# LegControleur.net
KiCad netlist of a schematic drawn in Altium Designer
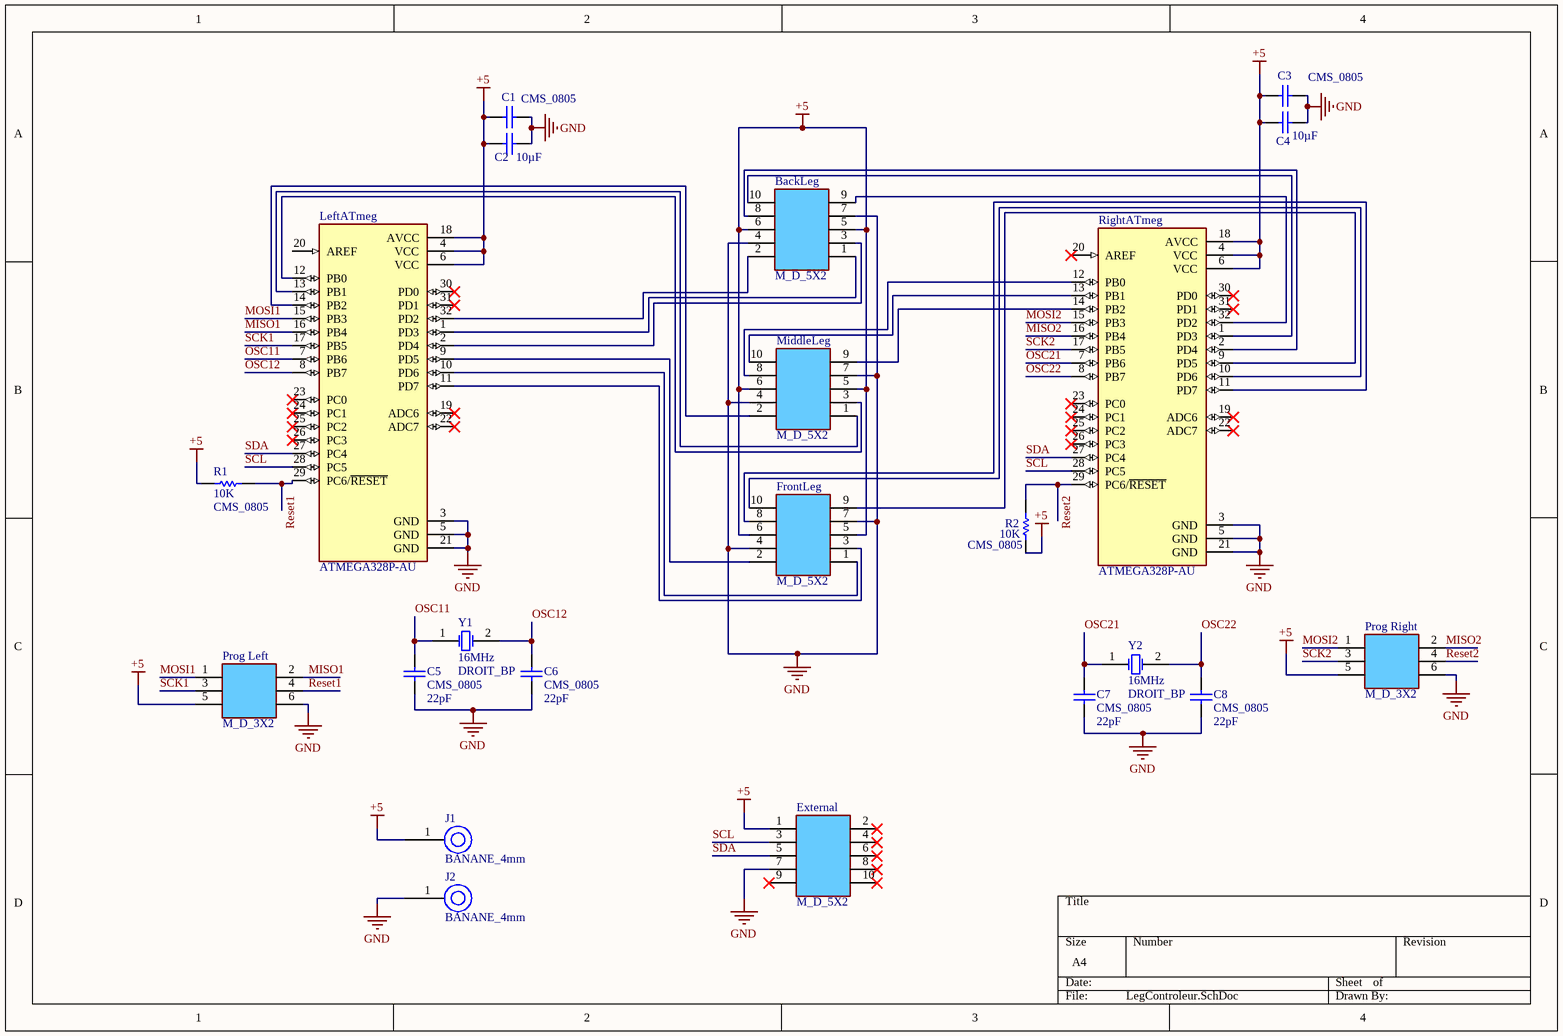
[diagram p0: LegControleur.SchDoc]

(export (version "E")
  (design (tool "Eeschema 10.0.6"))
  (components
    (comp (ref "BackLeg")
      (value "BARRETTE_5 CONTACTS_2 RANGEES_MALE_DROITE")
      (footprint "BARRETTE_5X2_M_D")
      (description "BARRETTE 5 CONTACTS 2 RANGEES MALE DROITE")
      (fields (field (name "TYPE") "M_D_5X2"))
      (libsource (lib "connecteurs") (part "BARRETTE_5 CONTACTS_2 RANGEES_MALE_DROITE"))
    )
    (comp (ref "C1")
      (value "10µF")
      (footprint "CONDENSATEUR_CMS_0805")
      (description "CONDENSATEUR CMS CERAMIQUE 0805")
      (fields (field (name "TYPE") "CMS_0805") (field (name "Comment") "CMS_0805_AVCC"))
      (libsource (lib "composants passifs") (part "CONDENSATEUR_CMS_CER_0805"))
    )
    (comp (ref "C2")
      (value "CMS_0805_VCC")
      (footprint "CONDENSATEUR_CMS_0805")
      (description "CONDENSATEUR CMS CERAMIQUE 0805")
      (libsource (lib "composants passifs") (part "CONDENSATEUR_CMS_CER_0805"))
    )
    (comp (ref "C3")
      (value "10µF")
      (footprint "CONDENSATEUR_CMS_0805")
      (description "CONDENSATEUR CMS CERAMIQUE 0805")
      (fields (field (name "TYPE") "CMS_0805") (field (name "Comment") "CMS_0805_AVCC"))
      (libsource (lib "composants passifs") (part "CONDENSATEUR_CMS_CER_0805"))
    )
    (comp (ref "C4")
      (value "CMS_0805_VCC")
      (footprint "CONDENSATEUR_CMS_0805")
      (description "CONDENSATEUR CMS CERAMIQUE 0805")
      (libsource (lib "composants passifs") (part "CONDENSATEUR_CMS_CER_0805"))
    )
    (comp (ref "C5")
      (value "22pF")
      (footprint "CONDENSATEUR_CMS_0805")
      (description "CONDENSATEUR CMS CERAMIQUE 0805")
      (fields (field (name "TYPE") "CMS_0805") (field (name "Comment") "CMS_0805"))
      (libsource (lib "composants passifs") (part "CONDENSATEUR_CMS_CER_0805"))
    )
    (comp (ref "C6")
      (value "22pF")
      (footprint "CONDENSATEUR_CMS_0805")
      (description "CONDENSATEUR CMS CERAMIQUE 0805")
      (fields (field (name "TYPE") "CMS_0805") (field (name "Comment") "CMS_0805"))
      (libsource (lib "composants passifs") (part "CONDENSATEUR_CMS_CER_0805"))
    )
    (comp (ref "C7")
      (value "22pF")
      (footprint "CONDENSATEUR_CMS_0805")
      (description "CONDENSATEUR CMS CERAMIQUE 0805")
      (fields (field (name "TYPE") "CMS_0805") (field (name "Comment") "CMS_0805"))
      (libsource (lib "composants passifs") (part "CONDENSATEUR_CMS_CER_0805"))
    )
    (comp (ref "C8")
      (value "22pF")
      (footprint "CONDENSATEUR_CMS_0805")
      (description "CONDENSATEUR CMS CERAMIQUE 0805")
      (fields (field (name "TYPE") "CMS_0805") (field (name "Comment") "CMS_0805"))
      (libsource (lib "composants passifs") (part "CONDENSATEUR_CMS_CER_0805"))
    )
    (comp (ref "External")
      (value "BARRETTE_5 CONTACTS_2 RANGEES_MALE_DROITE")
      (footprint "BARRETTE_5X2_M_D")
      (description "BARRETTE 5 CONTACTS 2 RANGEES MALE DROITE")
      (fields (field (name "TYPE") "M_D_5X2"))
      (libsource (lib "") (part "BARRETTE_5 CONTACTS_2 RANGEES_MALE_DROITE_1"))
    )
    (comp (ref "FrontLeg")
      (value "BARRETTE_5 CONTACTS_2 RANGEES_MALE_DROITE")
      (footprint "BARRETTE_5X2_M_D")
      (description "BARRETTE 5 CONTACTS 2 RANGEES MALE DROITE")
      (fields (field (name "TYPE") "M_D_5X2"))
      (libsource (lib "connecteurs") (part "BARRETTE_5 CONTACTS_2 RANGEES_MALE_DROITE"))
    )
    (comp (ref "J1")
      (value "Alim 5v")
      (footprint "DOUILLE_BANANE_4mm")
      (description "DOUILLE BANANE 4 mm")
      (fields (field (name "TYPE") "BANANE_4mm"))
      (libsource (lib "connecteurs") (part "DOUILLE_BANANE_4mm"))
    )
    (comp (ref "J2")
      (value "Alim GND")
      (footprint "DOUILLE_BANANE_4mm")
      (description "DOUILLE BANANE 4 mm")
      (fields (field (name "TYPE") "BANANE_4mm"))
      (libsource (lib "connecteurs") (part "DOUILLE_BANANE_4mm"))
    )
    (comp (ref "LeftATmeg")
      (value "ATMEGA328P-AU")
      (footprint "QFP80P900X900X120-32N")
      (description "AVR AVRÂ® ATmega Microcontroller IC 8-Bit 20MHz 32KB (16K x 16) FLASH 32-TQFP (7x7)")
      (fields (field (name "MF") "Microchip Technology"))
      (libsource (lib "ATMEGA328P-AU") (part "ATMEGA328P-AU"))
    )
    (comp (ref "MiddleLeg")
      (value "BARRETTE_5 CONTACTS_2 RANGEES_MALE_DROITE")
      (footprint "BARRETTE_5X2_M_D")
      (description "BARRETTE 5 CONTACTS 2 RANGEES MALE DROITE")
      (fields (field (name "TYPE") "M_D_5X2"))
      (libsource (lib "connecteurs") (part "BARRETTE_5 CONTACTS_2 RANGEES_MALE_DROITE"))
    )
    (comp (ref "Prog Left")
      (value "BARRETTE_3 CONTACTS_2 RANGEES_MALE_DROITE")
      (footprint "BARRETTE_3X2_M_D")
      (description "BARRETTE 3 CONTACTS 2 RANGEES MALE DROITE")
      (fields (field (name "TYPE") "M_D_3X2"))
      (libsource (lib "connecteurs") (part "BARRETTE_3 CONTACTS_2 RANGEES_MALE_DROITE"))
    )
    (comp (ref "Prog Right")
      (value "BARRETTE_3 CONTACTS_2 RANGEES_MALE_DROITE")
      (footprint "BARRETTE_3X2_M_D")
      (description "BARRETTE 3 CONTACTS 2 RANGEES MALE DROITE")
      (fields (field (name "TYPE") "M_D_3X2"))
      (libsource (lib "connecteurs") (part "BARRETTE_3 CONTACTS_2 RANGEES_MALE_DROITE"))
    )
    (comp (ref "R1")
      (value "10K")
      (footprint "RESISTANCE_CMS_0805")
      (description "RESISTANCE CMS 0805")
      (fields (field (name "TYPE") "CMS_0805") (field (name "Comment") "RESISTANCE_CMS_0805"))
      (libsource (lib "composants passifs") (part "RESISTANCE_CMS_0805"))
    )
    (comp (ref "R2")
      (value "10K")
      (footprint "RESISTANCE_CMS_0805")
      (description "RESISTANCE CMS 0805")
      (fields (field (name "TYPE") "CMS_0805") (field (name "Comment") "RESISTANCE_CMS_0805"))
      (libsource (lib "composants passifs") (part "RESISTANCE_CMS_0805"))
    )
    (comp (ref "RightATmeg")
      (value "ATMEGA328P-AU")
      (footprint "QFP80P900X900X120-32N")
      (description "AVR AVRÂ® ATmega Microcontroller IC 8-Bit 20MHz 32KB (16K x 16) FLASH 32-TQFP (7x7)")
      (fields (field (name "MF") "Microchip Technology"))
      (libsource (lib "ATMEGA328P-AU") (part "ATMEGA328P-AU"))
    )
    (comp (ref "Y1")
      (value "16MHz")
      (footprint "QUARTZ_DROIT_BP")
      (description "QUARTZ DROIT BAS PROFIL")
      (fields (field (name "TYPE") "DROIT_BP") (field (name "Comment") "QUARTZ_DROIT_BAS_PROFIL"))
      (libsource (lib "composants passifs") (part "QUARTZ_DROIT_BAS_PROFIL"))
    )
    (comp (ref "Y2")
      (value "16MHz")
      (footprint "QUARTZ_DROIT_BP")
      (description "QUARTZ DROIT BAS PROFIL")
      (fields (field (name "TYPE") "DROIT_BP") (field (name "Comment") "QUARTZ_DROIT_BAS_PROFIL"))
      (libsource (lib "composants passifs") (part "QUARTZ_DROIT_BAS_PROFIL"))
    )
  )
  (nets
    (net (code "1") (name "+5") (class "Default")
      (node (ref "BackLeg") (pin "5") (pinfunction "5_5") (pintype "passive"))
      (node (ref "BackLeg") (pin "6") (pinfunction "6_6") (pintype "passive"))
      (node (ref "C1") (pin "2") (pinfunction "2_2") (pintype "passive"))
      (node (ref "C2") (pin "2") (pinfunction "2_2") (pintype "passive"))
      (node (ref "C3") (pin "2") (pinfunction "2_2") (pintype "passive"))
      (node (ref "C4") (pin "2") (pinfunction "2_2") (pintype "passive"))
      (node (ref "External") (pin "1") (pinfunction "1_1") (pintype "passive"))
      (node (ref "FrontLeg") (pin "5") (pinfunction "5_5") (pintype "passive"))
      (node (ref "FrontLeg") (pin "6") (pinfunction "6_6") (pintype "passive"))
      (node (ref "J1") (pin "1") (pinfunction "1_1") (pintype "passive"))
      (node (ref "LeftATmeg") (pin "18") (pinfunction "AVCC_18") (pintype "power_in"))
      (node (ref "LeftATmeg") (pin "4") (pinfunction "VCC_4") (pintype "power_in"))
      (node (ref "LeftATmeg") (pin "6") (pinfunction "VCC_6") (pintype "power_in"))
      (node (ref "MiddleLeg") (pin "5") (pinfunction "5_5") (pintype "passive"))
      (node (ref "MiddleLeg") (pin "6") (pinfunction "6_6") (pintype "passive"))
      (node (ref "Prog Left") (pin "5") (pinfunction "5_5") (pintype "passive"))
      (node (ref "Prog Right") (pin "5") (pinfunction "5_5") (pintype "passive"))
      (node (ref "R1") (pin "1") (pinfunction "1_1") (pintype "passive"))
      (node (ref "R2") (pin "1") (pinfunction "1_1") (pintype "passive"))
      (node (ref "RightATmeg") (pin "18") (pinfunction "AVCC_18") (pintype "power_in"))
      (node (ref "RightATmeg") (pin "4") (pinfunction "VCC_4") (pintype "power_in"))
      (node (ref "RightATmeg") (pin "6") (pinfunction "VCC_6") (pintype "power_in"))
    )
    (net (code "2") (name "/MISO1") (class "Default")
      (node (ref "LeftATmeg") (pin "16") (pinfunction "PB4_16") (pintype "bidirectional"))
      (node (ref "Prog Left") (pin "2") (pinfunction "2_2") (pintype "passive"))
    )
    (net (code "3") (name "/MISO2") (class "Default")
      (node (ref "Prog Right") (pin "2") (pinfunction "2_2") (pintype "passive"))
      (node (ref "RightATmeg") (pin "16") (pinfunction "PB4_16") (pintype "bidirectional"))
    )
    (net (code "4") (name "/MOSI1") (class "Default")
      (node (ref "LeftATmeg") (pin "15") (pinfunction "PB3_15") (pintype "bidirectional"))
      (node (ref "Prog Left") (pin "1") (pinfunction "1_1") (pintype "passive"))
    )
    (net (code "5") (name "/MOSI2") (class "Default")
      (node (ref "Prog Right") (pin "1") (pinfunction "1_1") (pintype "passive"))
      (node (ref "RightATmeg") (pin "15") (pinfunction "PB3_15") (pintype "bidirectional"))
    )
    (net (code "6") (name "/OSC11") (class "Default")
      (node (ref "C5") (pin "2") (pinfunction "2_2") (pintype "passive"))
      (node (ref "LeftATmeg") (pin "7") (pinfunction "PB6_7") (pintype "bidirectional"))
      (node (ref "Y1") (pin "1") (pinfunction "OSC1_1") (pintype "passive"))
    )
    (net (code "7") (name "/OSC12") (class "Default")
      (node (ref "C6") (pin "2") (pinfunction "2_2") (pintype "passive"))
      (node (ref "LeftATmeg") (pin "8") (pinfunction "PB7_8") (pintype "bidirectional"))
      (node (ref "Y1") (pin "2") (pinfunction "OSC2_2") (pintype "passive"))
    )
    (net (code "8") (name "/OSC21") (class "Default")
      (node (ref "C7") (pin "2") (pinfunction "2_2") (pintype "passive"))
      (node (ref "RightATmeg") (pin "7") (pinfunction "PB6_7") (pintype "bidirectional"))
      (node (ref "Y2") (pin "1") (pinfunction "OSC1_1") (pintype "passive"))
    )
    (net (code "9") (name "/OSC22") (class "Default")
      (node (ref "C8") (pin "2") (pinfunction "2_2") (pintype "passive"))
      (node (ref "RightATmeg") (pin "8") (pinfunction "PB7_8") (pintype "bidirectional"))
      (node (ref "Y2") (pin "2") (pinfunction "OSC2_2") (pintype "passive"))
    )
    (net (code "10") (name "/Reset1") (class "Default")
      (node (ref "LeftATmeg") (pin "29") (pinfunction "PC6/~{RESET}_29") (pintype "bidirectional"))
      (node (ref "Prog Left") (pin "4") (pinfunction "4_4") (pintype "passive"))
      (node (ref "R1") (pin "2") (pinfunction "2_2") (pintype "passive"))
    )
    (net (code "11") (name "/Reset2") (class "Default")
      (node (ref "Prog Right") (pin "4") (pinfunction "4_4") (pintype "passive"))
      (node (ref "R2") (pin "2") (pinfunction "2_2") (pintype "passive"))
      (node (ref "RightATmeg") (pin "29") (pinfunction "PC6/~{RESET}_29") (pintype "bidirectional"))
    )
    (net (code "12") (name "/SCK1") (class "Default")
      (node (ref "LeftATmeg") (pin "17") (pinfunction "PB5_17") (pintype "bidirectional"))
      (node (ref "Prog Left") (pin "3") (pinfunction "3_3") (pintype "passive"))
    )
    (net (code "13") (name "/SCK2") (class "Default")
      (node (ref "Prog Right") (pin "3") (pinfunction "3_3") (pintype "passive"))
      (node (ref "RightATmeg") (pin "17") (pinfunction "PB5_17") (pintype "bidirectional"))
    )
    (net (code "14") (name "/SCL") (class "Default")
      (node (ref "External") (pin "3") (pinfunction "3_3") (pintype "passive"))
      (node (ref "LeftATmeg") (pin "28") (pinfunction "PC5_28") (pintype "bidirectional"))
      (node (ref "RightATmeg") (pin "28") (pinfunction "PC5_28") (pintype "bidirectional"))
    )
    (net (code "15") (name "/SDA") (class "Default")
      (node (ref "External") (pin "5") (pinfunction "5_5") (pintype "passive"))
      (node (ref "LeftATmeg") (pin "27") (pinfunction "PC4_27") (pintype "bidirectional"))
      (node (ref "RightATmeg") (pin "27") (pinfunction "PC4_27") (pintype "bidirectional"))
    )
    (net (code "16") (name "GND") (class "Default")
      (node (ref "BackLeg") (pin "4") (pinfunction "4_4") (pintype "passive"))
      (node (ref "BackLeg") (pin "7") (pinfunction "7_7") (pintype "passive"))
      (node (ref "C1") (pin "1") (pinfunction "1_1") (pintype "passive"))
      (node (ref "C2") (pin "1") (pinfunction "1_1") (pintype "passive"))
      (node (ref "C3") (pin "1") (pinfunction "1_1") (pintype "passive"))
      (node (ref "C4") (pin "1") (pinfunction "1_1") (pintype "passive"))
      (node (ref "C5") (pin "1") (pinfunction "1_1") (pintype "passive"))
      (node (ref "C6") (pin "1") (pinfunction "1_1") (pintype "passive"))
      (node (ref "C7") (pin "1") (pinfunction "1_1") (pintype "passive"))
      (node (ref "C8") (pin "1") (pinfunction "1_1") (pintype "passive"))
      (node (ref "External") (pin "7") (pinfunction "7_7") (pintype "passive"))
      (node (ref "FrontLeg") (pin "4") (pinfunction "4_4") (pintype "passive"))
      (node (ref "FrontLeg") (pin "7") (pinfunction "7_7") (pintype "passive"))
      (node (ref "J2") (pin "1") (pinfunction "1_1") (pintype "passive"))
      (node (ref "LeftATmeg") (pin "21") (pinfunction "GND_21") (pintype "power_in"))
      (node (ref "LeftATmeg") (pin "3") (pinfunction "GND_3") (pintype "power_in"))
      (node (ref "LeftATmeg") (pin "5") (pinfunction "GND_5") (pintype "power_in"))
      (node (ref "MiddleLeg") (pin "4") (pinfunction "4_4") (pintype "passive"))
      (node (ref "MiddleLeg") (pin "7") (pinfunction "7_7") (pintype "passive"))
      (node (ref "Prog Left") (pin "6") (pinfunction "6_6") (pintype "passive"))
      (node (ref "Prog Right") (pin "6") (pinfunction "6_6") (pintype "passive"))
      (node (ref "RightATmeg") (pin "21") (pinfunction "GND_21") (pintype "power_in"))
      (node (ref "RightATmeg") (pin "3") (pinfunction "GND_3") (pintype "power_in"))
      (node (ref "RightATmeg") (pin "5") (pinfunction "GND_5") (pintype "power_in"))
    )
    (net (code "17") (name "Net-(LeftATmeg-PB0)") (class "Default")
      (node (ref "LeftATmeg") (pin "12") (pinfunction "PB0_12") (pintype "bidirectional"))
      (node (ref "MiddleLeg") (pin "3") (pinfunction "3_3") (pintype "passive"))
    )
    (net (code "18") (name "Net-(LeftATmeg-PB1)") (class "Default")
      (node (ref "LeftATmeg") (pin "13") (pinfunction "PB1_13") (pintype "bidirectional"))
      (node (ref "MiddleLeg") (pin "1") (pinfunction "1_1") (pintype "passive"))
    )
    (net (code "19") (name "Net-(LeftATmeg-PB2)") (class "Default")
      (node (ref "LeftATmeg") (pin "14") (pinfunction "PB2_14") (pintype "bidirectional"))
      (node (ref "MiddleLeg") (pin "2") (pinfunction "2_2") (pintype "passive"))
    )
    (net (code "20") (name "Net-(LeftATmeg-PD2)") (class "Default")
      (node (ref "BackLeg") (pin "2") (pinfunction "2_2") (pintype "passive"))
      (node (ref "LeftATmeg") (pin "32") (pinfunction "PD2_32") (pintype "bidirectional"))
    )
    (net (code "21") (name "Net-(LeftATmeg-PD3)") (class "Default")
      (node (ref "BackLeg") (pin "1") (pinfunction "1_1") (pintype "passive"))
      (node (ref "LeftATmeg") (pin "1") (pinfunction "PD3_1") (pintype "bidirectional"))
    )
    (net (code "22") (name "Net-(LeftATmeg-PD4)") (class "Default")
      (node (ref "BackLeg") (pin "3") (pinfunction "3_3") (pintype "passive"))
      (node (ref "LeftATmeg") (pin "2") (pinfunction "PD4_2") (pintype "bidirectional"))
    )
    (net (code "23") (name "Net-(LeftATmeg-PD5)") (class "Default")
      (node (ref "FrontLeg") (pin "2") (pinfunction "2_2") (pintype "passive"))
      (node (ref "LeftATmeg") (pin "9") (pinfunction "PD5_9") (pintype "bidirectional"))
    )
    (net (code "24") (name "Net-(LeftATmeg-PD6)") (class "Default")
      (node (ref "FrontLeg") (pin "1") (pinfunction "1_1") (pintype "passive"))
      (node (ref "LeftATmeg") (pin "10") (pinfunction "PD6_10") (pintype "bidirectional"))
    )
    (net (code "25") (name "Net-(LeftATmeg-PD7)") (class "Default")
      (node (ref "FrontLeg") (pin "3") (pinfunction "3_3") (pintype "passive"))
      (node (ref "LeftATmeg") (pin "11") (pinfunction "PD7_11") (pintype "bidirectional"))
    )
    (net (code "26") (name "Net-(RightATmeg-PB0)") (class "Default")
      (node (ref "MiddleLeg") (pin "8") (pinfunction "8_8") (pintype "passive"))
      (node (ref "RightATmeg") (pin "12") (pinfunction "PB0_12") (pintype "bidirectional"))
    )
    (net (code "27") (name "Net-(RightATmeg-PB1)") (class "Default")
      (node (ref "MiddleLeg") (pin "10") (pinfunction "10_10") (pintype "passive"))
      (node (ref "RightATmeg") (pin "13") (pinfunction "PB1_13") (pintype "bidirectional"))
    )
    (net (code "28") (name "Net-(RightATmeg-PB2)") (class "Default")
      (node (ref "MiddleLeg") (pin "9") (pinfunction "9_9") (pintype "passive"))
      (node (ref "RightATmeg") (pin "14") (pinfunction "PB2_14") (pintype "bidirectional"))
    )
    (net (code "29") (name "Net-(RightATmeg-PD2)") (class "Default")
      (node (ref "BackLeg") (pin "9") (pinfunction "9_9") (pintype "passive"))
      (node (ref "RightATmeg") (pin "32") (pinfunction "PD2_32") (pintype "bidirectional"))
    )
    (net (code "30") (name "Net-(RightATmeg-PD3)") (class "Default")
      (node (ref "BackLeg") (pin "10") (pinfunction "10_10") (pintype "passive"))
      (node (ref "RightATmeg") (pin "1") (pinfunction "PD3_1") (pintype "bidirectional"))
    )
    (net (code "31") (name "Net-(RightATmeg-PD4)") (class "Default")
      (node (ref "BackLeg") (pin "8") (pinfunction "8_8") (pintype "passive"))
      (node (ref "RightATmeg") (pin "2") (pinfunction "PD4_2") (pintype "bidirectional"))
    )
    (net (code "32") (name "Net-(RightATmeg-PD5)") (class "Default")
      (node (ref "FrontLeg") (pin "9") (pinfunction "9_9") (pintype "passive"))
      (node (ref "RightATmeg") (pin "9") (pinfunction "PD5_9") (pintype "bidirectional"))
    )
    (net (code "33") (name "Net-(RightATmeg-PD6)") (class "Default")
      (node (ref "FrontLeg") (pin "10") (pinfunction "10_10") (pintype "passive"))
      (node (ref "RightATmeg") (pin "10") (pinfunction "PD6_10") (pintype "bidirectional"))
    )
    (net (code "34") (name "Net-(RightATmeg-PD7)") (class "Default")
      (node (ref "FrontLeg") (pin "8") (pinfunction "8_8") (pintype "passive"))
      (node (ref "RightATmeg") (pin "11") (pinfunction "PD7_11") (pintype "bidirectional"))
    )
    (net (code "35") (name "unconnected-(External-Pad2)") (class "Default")
      (node (ref "External") (pin "2") (pinfunction "2_2") (pintype "passive+no_connect"))
    )
    (net (code "36") (name "unconnected-(External-Pad4)") (class "Default")
      (node (ref "External") (pin "4") (pinfunction "4_4") (pintype "passive+no_connect"))
    )
    (net (code "37") (name "unconnected-(External-Pad6)") (class "Default")
      (node (ref "External") (pin "6") (pinfunction "6_6") (pintype "passive+no_connect"))
    )
    (net (code "38") (name "unconnected-(External-Pad8)") (class "Default")
      (node (ref "External") (pin "8") (pinfunction "8_8") (pintype "passive+no_connect"))
    )
    (net (code "39") (name "unconnected-(External-Pad9)") (class "Default")
      (node (ref "External") (pin "9") (pinfunction "9_9") (pintype "passive+no_connect"))
    )
    (net (code "40") (name "unconnected-(External-Pad10)") (class "Default")
      (node (ref "External") (pin "10") (pinfunction "10_10") (pintype "passive+no_connect"))
    )
    (net (code "41") (name "unconnected-(LeftATmeg-ADC6-Pad19)") (class "Default")
      (node (ref "LeftATmeg") (pin "19") (pinfunction "ADC6_19") (pintype "bidirectional+no_connect"))
    )
    (net (code "42") (name "unconnected-(LeftATmeg-ADC7-Pad22)") (class "Default")
      (node (ref "LeftATmeg") (pin "22") (pinfunction "ADC7_22") (pintype "bidirectional+no_connect"))
    )
    (net (code "43") (name "unconnected-(LeftATmeg-AREF-Pad20)") (class "Default")
      (node (ref "LeftATmeg") (pin "20") (pinfunction "AREF_20") (pintype "input"))
    )
    (net (code "44") (name "unconnected-(LeftATmeg-PC0-Pad23)") (class "Default")
      (node (ref "LeftATmeg") (pin "23") (pinfunction "PC0_23") (pintype "bidirectional+no_connect"))
    )
    (net (code "45") (name "unconnected-(LeftATmeg-PC1-Pad24)") (class "Default")
      (node (ref "LeftATmeg") (pin "24") (pinfunction "PC1_24") (pintype "bidirectional+no_connect"))
    )
    (net (code "46") (name "unconnected-(LeftATmeg-PC2-Pad25)") (class "Default")
      (node (ref "LeftATmeg") (pin "25") (pinfunction "PC2_25") (pintype "bidirectional+no_connect"))
    )
    (net (code "47") (name "unconnected-(LeftATmeg-PC3-Pad26)") (class "Default")
      (node (ref "LeftATmeg") (pin "26") (pinfunction "PC3_26") (pintype "bidirectional+no_connect"))
    )
    (net (code "48") (name "unconnected-(LeftATmeg-PD0-Pad30)") (class "Default")
      (node (ref "LeftATmeg") (pin "30") (pinfunction "PD0_30") (pintype "bidirectional+no_connect"))
    )
    (net (code "49") (name "unconnected-(LeftATmeg-PD1-Pad31)") (class "Default")
      (node (ref "LeftATmeg") (pin "31") (pinfunction "PD1_31") (pintype "bidirectional+no_connect"))
    )
    (net (code "50") (name "unconnected-(RightATmeg-ADC6-Pad19)") (class "Default")
      (node (ref "RightATmeg") (pin "19") (pinfunction "ADC6_19") (pintype "bidirectional+no_connect"))
    )
    (net (code "51") (name "unconnected-(RightATmeg-ADC7-Pad22)") (class "Default")
      (node (ref "RightATmeg") (pin "22") (pinfunction "ADC7_22") (pintype "bidirectional+no_connect"))
    )
    (net (code "52") (name "unconnected-(RightATmeg-AREF-Pad20)") (class "Default")
      (node (ref "RightATmeg") (pin "20") (pinfunction "AREF_20") (pintype "input+no_connect"))
    )
    (net (code "53") (name "unconnected-(RightATmeg-PC0-Pad23)") (class "Default")
      (node (ref "RightATmeg") (pin "23") (pinfunction "PC0_23") (pintype "bidirectional+no_connect"))
    )
    (net (code "54") (name "unconnected-(RightATmeg-PC1-Pad24)") (class "Default")
      (node (ref "RightATmeg") (pin "24") (pinfunction "PC1_24") (pintype "bidirectional+no_connect"))
    )
    (net (code "55") (name "unconnected-(RightATmeg-PC2-Pad25)") (class "Default")
      (node (ref "RightATmeg") (pin "25") (pinfunction "PC2_25") (pintype "bidirectional+no_connect"))
    )
    (net (code "56") (name "unconnected-(RightATmeg-PC3-Pad26)") (class "Default")
      (node (ref "RightATmeg") (pin "26") (pinfunction "PC3_26") (pintype "bidirectional+no_connect"))
    )
    (net (code "57") (name "unconnected-(RightATmeg-PD0-Pad30)") (class "Default")
      (node (ref "RightATmeg") (pin "30") (pinfunction "PD0_30") (pintype "bidirectional+no_connect"))
    )
    (net (code "58") (name "unconnected-(RightATmeg-PD1-Pad31)") (class "Default")
      (node (ref "RightATmeg") (pin "31") (pinfunction "PD1_31") (pintype "bidirectional+no_connect"))
    )
  )
)
